# SPY_SCH.net
KiCad netlist of a schematic drawn in EAGLE
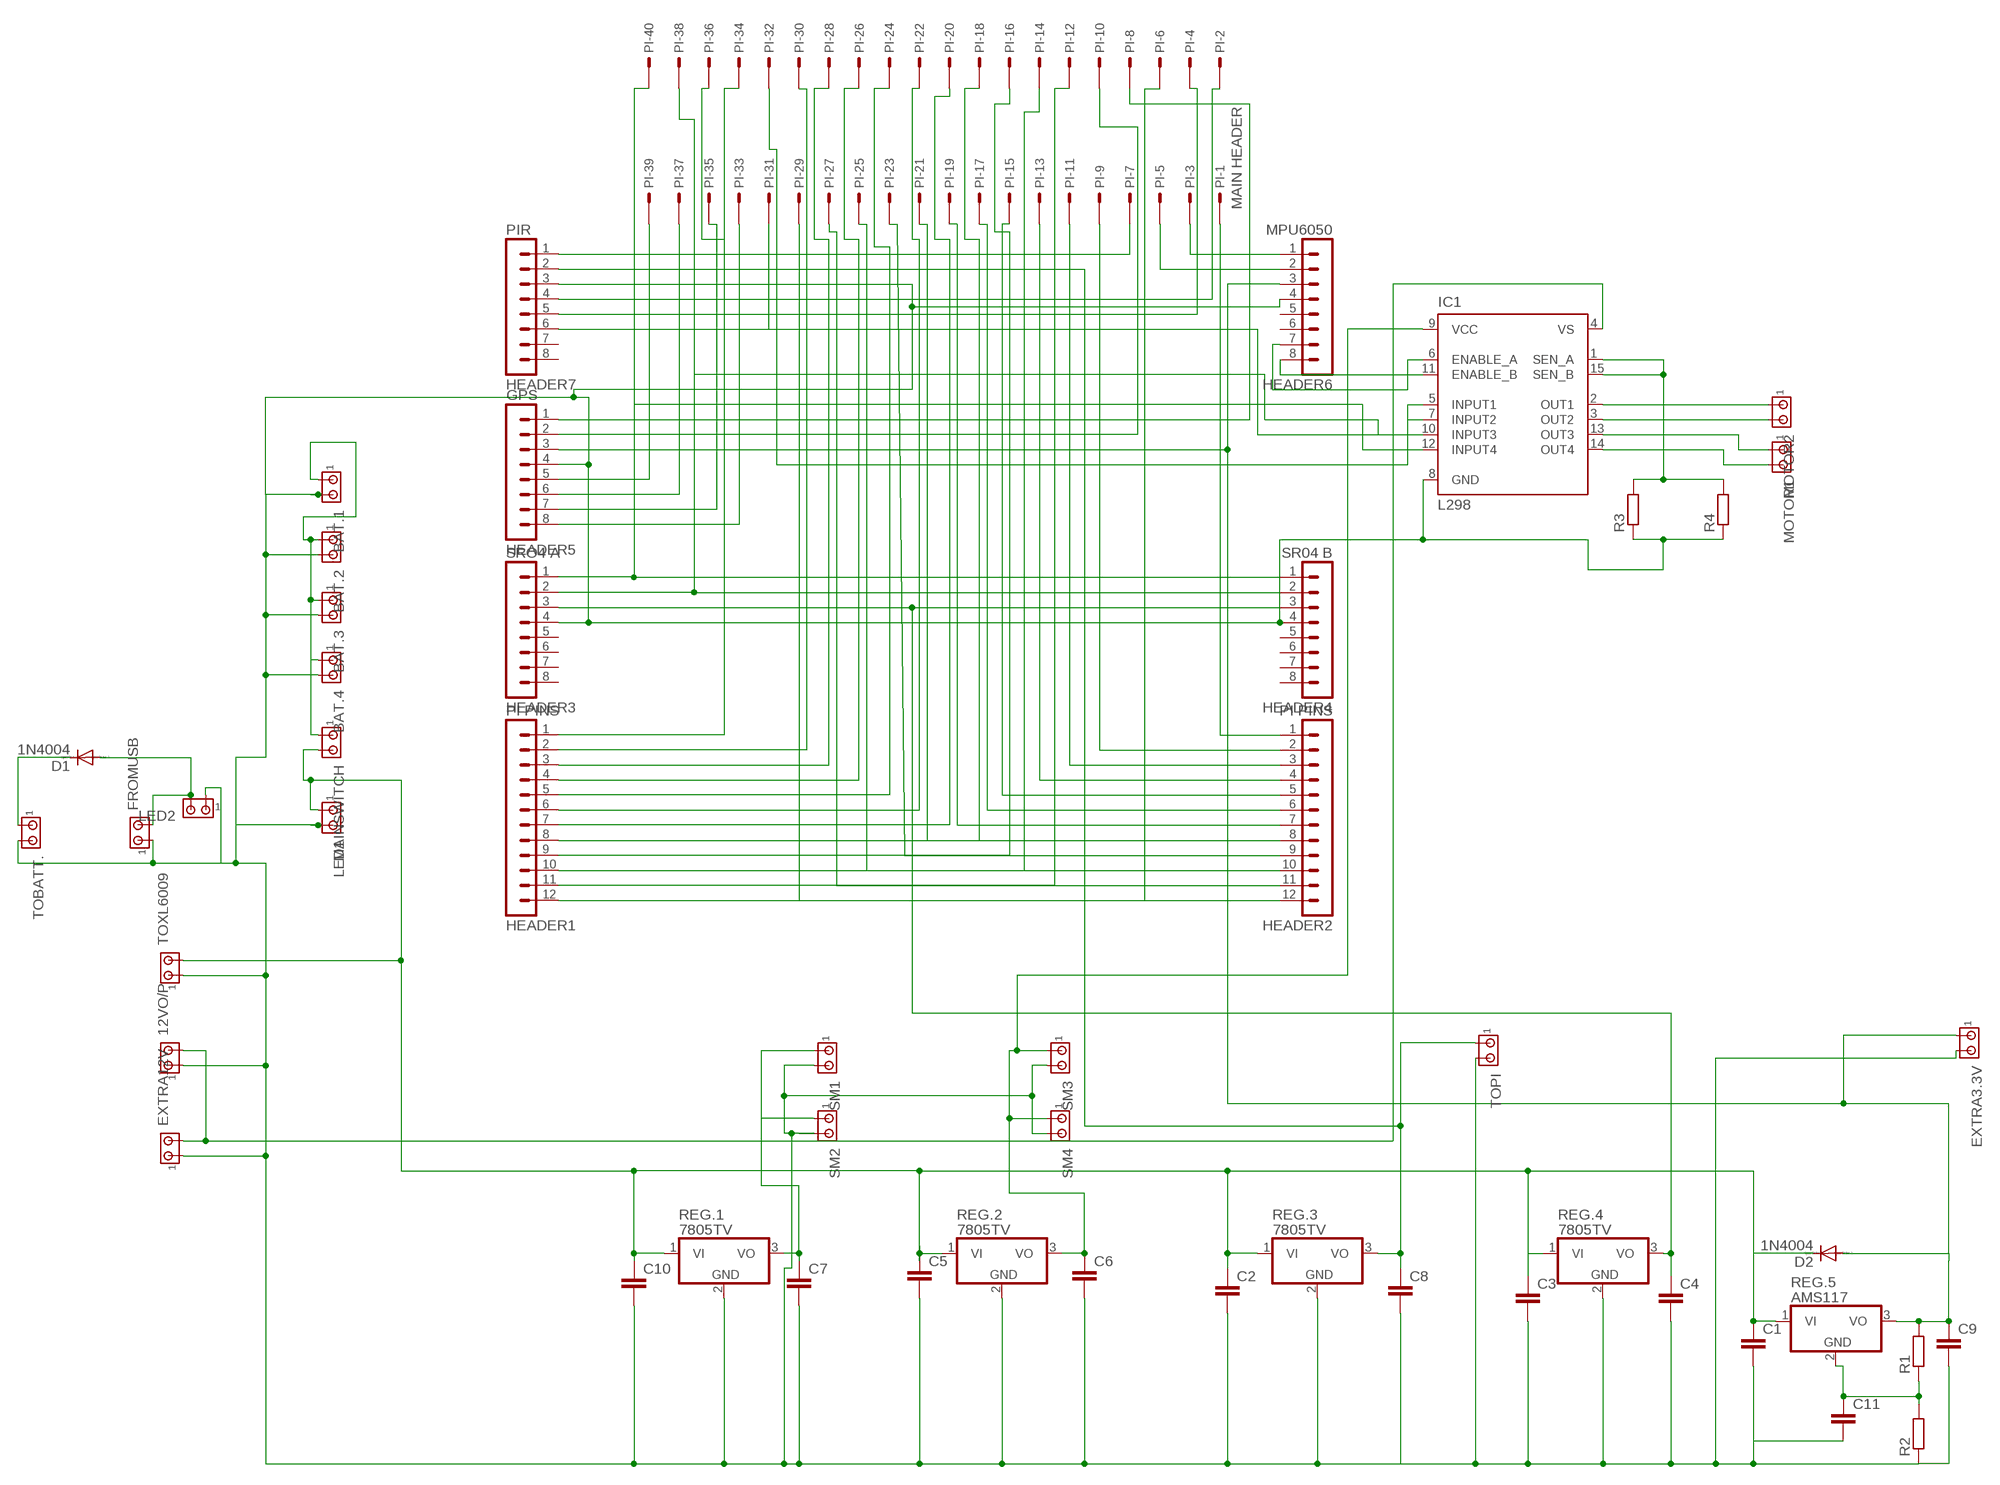
[diagram p0: schematic, sheet 1]

(export (version "E")
  (design (tool "Eeschema 10.0.6"))
  (components
    (comp (ref "12VO/P")
      (value "MTA02-156")
      (footprint "eagle-import:1X2MTA")
      (libsource (lib "eagle-import") (part "MTA02-156"))
    )
    (comp (ref "BAT.1")
      (value "MTA02-156")
      (footprint "eagle-import:1X2MTA")
      (libsource (lib "eagle-import") (part "MTA02-156"))
    )
    (comp (ref "BAT.2")
      (value "MTA02-156")
      (footprint "eagle-import:1X2MTA")
      (libsource (lib "eagle-import") (part "MTA02-156"))
    )
    (comp (ref "BAT.3")
      (value "MTA02-156")
      (footprint "eagle-import:1X2MTA")
      (libsource (lib "eagle-import") (part "MTA02-156"))
    )
    (comp (ref "BAT.4")
      (value "MTA02-156")
      (footprint "eagle-import:1X2MTA")
      (libsource (lib "eagle-import") (part "MTA02-156"))
    )
    (comp (ref "C1")
      (value "C2,5-3")
      (footprint "eagle-import:C2.5-3")
      (libsource (lib "eagle-import") (part "C2,5-3"))
    )
    (comp (ref "C2")
      (value "C2,5-3")
      (footprint "eagle-import:C2.5-3")
      (libsource (lib "eagle-import") (part "C2,5-3"))
    )
    (comp (ref "C3")
      (value "C2,5-3")
      (footprint "eagle-import:C2.5-3")
      (libsource (lib "eagle-import") (part "C2,5-3"))
    )
    (comp (ref "C4")
      (value "C2,5-3")
      (footprint "eagle-import:C2.5-3")
      (libsource (lib "eagle-import") (part "C2,5-3"))
    )
    (comp (ref "C5")
      (value "C2,5-3")
      (footprint "eagle-import:C2.5-3")
      (libsource (lib "eagle-import") (part "C2,5-3"))
    )
    (comp (ref "C6")
      (value "C2,5-3")
      (footprint "eagle-import:C2.5-3")
      (libsource (lib "eagle-import") (part "C2,5-3"))
    )
    (comp (ref "C7")
      (value "C2,5-3")
      (footprint "eagle-import:C2.5-3")
      (libsource (lib "eagle-import") (part "C2,5-3"))
    )
    (comp (ref "C8")
      (value "C2,5-3")
      (footprint "eagle-import:C2.5-3")
      (libsource (lib "eagle-import") (part "C2,5-3"))
    )
    (comp (ref "C9")
      (value "C2,5-3")
      (footprint "eagle-import:C2.5-3")
      (libsource (lib "eagle-import") (part "C2,5-3"))
    )
    (comp (ref "C10")
      (value "C2,5-3")
      (footprint "eagle-import:C2.5-3")
      (libsource (lib "eagle-import") (part "C2,5-3"))
    )
    (comp (ref "C11")
      (value "C2,5-3")
      (footprint "eagle-import:C2.5-3")
      (libsource (lib "eagle-import") (part "C2,5-3"))
    )
    (comp (ref "D1")
      (value "1N4004")
      (footprint "eagle-import:DO41-10")
      (libsource (lib "eagle-import") (part "1N4004"))
    )
    (comp (ref "D2")
      (value "1N4004")
      (footprint "eagle-import:DO41-10")
      (libsource (lib "eagle-import") (part "1N4004"))
    )
    (comp (ref "EXTRA3.3V")
      (value "MTA02-156")
      (footprint "eagle-import:1X2MTA")
      (libsource (lib "eagle-import") (part "MTA02-156"))
    )
    (comp (ref "EXTRA12V")
      (value "MTA02-156")
      (footprint "eagle-import:1X2MTA")
      (libsource (lib "eagle-import") (part "MTA02-156"))
    )
    (comp (ref "FROMUSB")
      (value "MTA02-156")
      (footprint "eagle-import:1X2MTA")
      (libsource (lib "eagle-import") (part "MTA02-156"))
    )
    (comp (ref "HEADER1")
      (value "PI PINS")
      (footprint "eagle-import:MA12-1W")
      (libsource (lib "eagle-import") (part "MA12-1W"))
    )
    (comp (ref "HEADER2")
      (value "PI PINS")
      (footprint "eagle-import:MA12-1W")
      (libsource (lib "eagle-import") (part "MA12-1W"))
    )
    (comp (ref "HEADER3")
      (value "SRO4 A")
      (footprint "eagle-import:MA08-1")
      (libsource (lib "eagle-import") (part "MA08-1"))
    )
    (comp (ref "HEADER4")
      (value "SR04 B")
      (footprint "eagle-import:MA08-1")
      (libsource (lib "eagle-import") (part "MA08-1"))
    )
    (comp (ref "HEADER5")
      (value "GPS")
      (footprint "eagle-import:MA08-1")
      (libsource (lib "eagle-import") (part "MA08-1"))
    )
    (comp (ref "HEADER6")
      (value "MPU6050")
      (footprint "eagle-import:MA08-1")
      (libsource (lib "eagle-import") (part "MA08-1"))
    )
    (comp (ref "HEADER7")
      (value "PIR")
      (footprint "eagle-import:MA08-1")
      (libsource (lib "eagle-import") (part "MA08-1"))
    )
    (comp (ref "IC1")
      (value "L298")
      (footprint "eagle-import:MULTIWATT-15")
      (fields (field (name "MPN") "L298N"))
      (libsource (lib "eagle-import") (part "L298"))
    )
    (comp (ref "LED1")
      (value "MTA02-156")
      (footprint "eagle-import:1X2MTA")
      (libsource (lib "eagle-import") (part "MTA02-156"))
    )
    (comp (ref "LED2")
      (value "MTA02-156")
      (footprint "eagle-import:1X2MTA")
      (libsource (lib "eagle-import") (part "MTA02-156"))
    )
    (comp (ref "MAINSWITCH")
      (value "MTA02-156")
      (footprint "eagle-import:1X2MTA")
      (libsource (lib "eagle-import") (part "MTA02-156"))
    )
    (comp (ref "MOTOR1")
      (value "MTA02-156")
      (footprint "eagle-import:1X2MTA")
      (libsource (lib "eagle-import") (part "MTA02-156"))
    )
    (comp (ref "MOTOR2")
      (value "MTA02-156")
      (footprint "eagle-import:1X2MTA")
      (libsource (lib "eagle-import") (part "MTA02-156"))
    )
    (comp (ref "PI")
      (value "MAIN HEADER")
      (footprint "eagle-import:057-040-1")
      (libsource (lib "eagle-import") (part "057-040-1"))
    )
    (comp (ref "R1")
      (value "R-EU_0309/12")
      (footprint "eagle-import:0309_12")
      (libsource (lib "eagle-import") (part "R-EU_0309/12"))
    )
    (comp (ref "R2")
      (value "R-EU_0309/12")
      (footprint "eagle-import:0309_12")
      (libsource (lib "eagle-import") (part "R-EU_0309/12"))
    )
    (comp (ref "R3")
      (value "R-EU_0309/12")
      (footprint "eagle-import:0309_12")
      (libsource (lib "eagle-import") (part "R-EU_0309/12"))
    )
    (comp (ref "R4")
      (value "R-EU_0309/12")
      (footprint "eagle-import:0309_12")
      (libsource (lib "eagle-import") (part "R-EU_0309/12"))
    )
    (comp (ref "REG.1")
      (value "7805TV")
      (footprint "eagle-import:TO220V")
      (libsource (lib "eagle-import") (part "78TV05"))
    )
    (comp (ref "REG.2")
      (value "7805TV")
      (footprint "eagle-import:TO220V")
      (libsource (lib "eagle-import") (part "78TV05"))
    )
    (comp (ref "REG.3")
      (value "7805TV")
      (footprint "eagle-import:TO220V")
      (libsource (lib "eagle-import") (part "78TV05"))
    )
    (comp (ref "REG.4")
      (value "7805TV")
      (footprint "eagle-import:TO220V")
      (libsource (lib "eagle-import") (part "78TV05"))
    )
    (comp (ref "REG.5")
      (value "AMS117")
      (footprint "eagle-import:TO220V")
      (libsource (lib "eagle-import") (part "78TV05"))
    )
    (comp (ref "SM1")
      (value "MTA02-156")
      (footprint "eagle-import:1X2MTA")
      (libsource (lib "eagle-import") (part "MTA02-156"))
    )
    (comp (ref "SM2")
      (value "MTA02-156")
      (footprint "eagle-import:1X2MTA")
      (libsource (lib "eagle-import") (part "MTA02-156"))
    )
    (comp (ref "SM3")
      (value "MTA02-156")
      (footprint "eagle-import:1X2MTA")
      (libsource (lib "eagle-import") (part "MTA02-156"))
    )
    (comp (ref "SM4")
      (value "MTA02-156")
      (footprint "eagle-import:1X2MTA")
      (libsource (lib "eagle-import") (part "MTA02-156"))
    )
    (comp (ref "TOBATT.")
      (value "MTA02-156")
      (footprint "eagle-import:1X2MTA")
      (libsource (lib "eagle-import") (part "MTA02-156"))
    )
    (comp (ref "TOPI")
      (value "MTA02-156")
      (footprint "eagle-import:1X2MTA")
      (libsource (lib "eagle-import") (part "MTA02-156"))
    )
    (comp (ref "TOXL6009")
      (value "MTA02-156")
      (footprint "eagle-import:1X2MTA")
      (libsource (lib "eagle-import") (part "MTA02-156"))
    )
  )
  (nets
    (net (code "1") (name "Net-(BAT.1-Pad1)") (class "Default")
      (node (ref "BAT.1") (pin "1") (pinfunction "1_1") (pintype "passive"))
      (node (ref "BAT.2") (pin "1") (pinfunction "1_1") (pintype "passive"))
      (node (ref "BAT.3") (pin "1") (pinfunction "1_1") (pintype "passive"))
      (node (ref "BAT.4") (pin "1") (pinfunction "1_1") (pintype "passive"))
      (node (ref "MAINSWITCH") (pin "1") (pinfunction "1_1") (pintype "passive"))
    )
    (net (code "2") (name "Net-(D1-PadA)") (class "Default")
      (node (ref "D1") (pin "A") (pinfunction "A_A") (pintype "passive"))
      (node (ref "FROMUSB") (pin "2") (pinfunction "2_2") (pintype "passive"))
      (node (ref "LED2") (pin "2") (pinfunction "2_2") (pintype "passive"))
    )
    (net (code "3") (name "Net-(D1-PadC)") (class "Default")
      (node (ref "D1") (pin "C") (pinfunction "C_C") (pintype "passive"))
      (node (ref "TOBATT.") (pin "1") (pinfunction "1_1") (pintype "passive"))
    )
    (net (code "4") (name "Net-(IC1-ENABLE_A)") (class "Default")
      (node (ref "HEADER6") (pin "7") (pinfunction "7_7") (pintype "passive"))
      (node (ref "IC1") (pin "6") (pinfunction "ENABLE_A_6") (pintype "input"))
    )
    (net (code "5") (name "Net-(IC1-ENABLE_B)") (class "Default")
      (node (ref "HEADER6") (pin "8") (pinfunction "8_8") (pintype "passive"))
      (node (ref "IC1") (pin "11") (pinfunction "ENABLE_B_11") (pintype "input"))
    )
    (net (code "6") (name "Net-(IC1-GND)") (class "Default")
      (node (ref "12VO/P") (pin "1") (pinfunction "1_1") (pintype "passive"))
      (node (ref "BAT.1") (pin "2") (pinfunction "2_2") (pintype "passive"))
      (node (ref "BAT.2") (pin "2") (pinfunction "2_2") (pintype "passive"))
      (node (ref "BAT.3") (pin "2") (pinfunction "2_2") (pintype "passive"))
      (node (ref "BAT.4") (pin "2") (pinfunction "2_2") (pintype "passive"))
      (node (ref "C1") (pin "2") (pinfunction "2_2") (pintype "passive"))
      (node (ref "C10") (pin "2") (pinfunction "2_2") (pintype "passive"))
      (node (ref "C11") (pin "2") (pinfunction "2_2") (pintype "passive"))
      (node (ref "C2") (pin "2") (pinfunction "2_2") (pintype "passive"))
      (node (ref "C3") (pin "2") (pinfunction "2_2") (pintype "passive"))
      (node (ref "C4") (pin "2") (pinfunction "2_2") (pintype "passive"))
      (node (ref "C5") (pin "2") (pinfunction "2_2") (pintype "passive"))
      (node (ref "C6") (pin "2") (pinfunction "2_2") (pintype "passive"))
      (node (ref "C7") (pin "2") (pinfunction "2_2") (pintype "passive"))
      (node (ref "C8") (pin "2") (pinfunction "2_2") (pintype "passive"))
      (node (ref "C9") (pin "2") (pinfunction "2_2") (pintype "passive"))
      (node (ref "EXTRA12V") (pin "1") (pinfunction "1_1") (pintype "passive"))
      (node (ref "EXTRA3.3V") (pin "2") (pinfunction "2_2") (pintype "passive"))
      (node (ref "FROMUSB") (pin "1") (pinfunction "1_1") (pintype "passive"))
      (node (ref "HEADER3") (pin "4") (pinfunction "4_4") (pintype "passive"))
      (node (ref "HEADER4") (pin "4") (pinfunction "4_4") (pintype "passive"))
      (node (ref "HEADER5") (pin "4") (pinfunction "4_4") (pintype "passive"))
      (node (ref "HEADER6") (pin "4") (pinfunction "4_4") (pintype "passive"))
      (node (ref "HEADER7") (pin "3") (pinfunction "3_3") (pintype "passive"))
      (node (ref "IC1") (pin "8") (pinfunction "GND_8") (pintype "power_in"))
      (node (ref "LED1") (pin "2") (pinfunction "2_2") (pintype "passive"))
      (node (ref "LED2") (pin "1") (pinfunction "1_1") (pintype "passive"))
      (node (ref "R2") (pin "1") (pinfunction "1_1") (pintype "passive"))
      (node (ref "R3") (pin "1") (pinfunction "1_1") (pintype "passive"))
      (node (ref "R4") (pin "1") (pinfunction "1_1") (pintype "passive"))
      (node (ref "REG.1") (pin "2") (pinfunction "GND_2") (pintype "passive"))
      (node (ref "REG.2") (pin "2") (pinfunction "GND_2") (pintype "passive"))
      (node (ref "REG.3") (pin "2") (pinfunction "GND_2") (pintype "passive"))
      (node (ref "REG.4") (pin "2") (pinfunction "GND_2") (pintype "passive"))
      (node (ref "SM1") (pin "2") (pinfunction "2_2") (pintype "passive"))
      (node (ref "SM2") (pin "2") (pinfunction "2_2") (pintype "passive"))
      (node (ref "SM3") (pin "2") (pinfunction "2_2") (pintype "passive"))
      (node (ref "SM4") (pin "2") (pinfunction "2_2") (pintype "passive"))
      (node (ref "TOBATT.") (pin "2") (pinfunction "2_2") (pintype "passive"))
      (node (ref "TOPI") (pin "2") (pinfunction "2_2") (pintype "passive"))
      (node (ref "TOXL6009") (pin "1") (pinfunction "1_1") (pintype "passive"))
    )
    (net (code "7") (name "Net-(IC1-INPUT1)") (class "Default")
      (node (ref "IC1") (pin "5") (pinfunction "INPUT1_5") (pintype "input"))
      (node (ref "PI") (pin "32") (pinfunction "S_32") (pintype "passive"))
    )
    (net (code "8") (name "Net-(IC1-INPUT2)") (class "Default")
      (node (ref "IC1") (pin "7") (pinfunction "INPUT2_7") (pintype "input"))
      (node (ref "PI") (pin "36") (pinfunction "S_36") (pintype "passive"))
    )
    (net (code "9") (name "Net-(IC1-INPUT3)") (class "Default")
      (node (ref "HEADER3") (pin "2") (pinfunction "2_2") (pintype "passive"))
      (node (ref "HEADER4") (pin "2") (pinfunction "2_2") (pintype "passive"))
      (node (ref "IC1") (pin "10") (pinfunction "INPUT3_10") (pintype "input"))
      (node (ref "PI") (pin "38") (pinfunction "S_38") (pintype "passive"))
    )
    (net (code "10") (name "Net-(IC1-INPUT4)") (class "Default")
      (node (ref "HEADER3") (pin "1") (pinfunction "1_1") (pintype "passive"))
      (node (ref "HEADER4") (pin "1") (pinfunction "1_1") (pintype "passive"))
      (node (ref "IC1") (pin "12") (pinfunction "INPUT4_12") (pintype "input"))
      (node (ref "PI") (pin "40") (pinfunction "S_40") (pintype "passive"))
    )
    (net (code "11") (name "Net-(IC1-OUT1)") (class "Default")
      (node (ref "IC1") (pin "2") (pinfunction "OUT1_2") (pintype "output"))
      (node (ref "MOTOR2") (pin "1") (pinfunction "1_1") (pintype "passive"))
    )
    (net (code "12") (name "Net-(IC1-OUT2)") (class "Default")
      (node (ref "IC1") (pin "3") (pinfunction "OUT2_3") (pintype "output"))
      (node (ref "MOTOR2") (pin "2") (pinfunction "2_2") (pintype "passive"))
    )
    (net (code "13") (name "Net-(IC1-OUT3)") (class "Default")
      (node (ref "IC1") (pin "13") (pinfunction "OUT3_13") (pintype "output"))
      (node (ref "MOTOR1") (pin "1") (pinfunction "1_1") (pintype "passive"))
    )
    (net (code "14") (name "Net-(IC1-OUT4)") (class "Default")
      (node (ref "IC1") (pin "14") (pinfunction "OUT4_14") (pintype "output"))
      (node (ref "MOTOR1") (pin "2") (pinfunction "2_2") (pintype "passive"))
    )
    (net (code "15") (name "Net-(IC1-SEN_A)") (class "Default")
      (node (ref "IC1") (pin "1") (pinfunction "SEN_A_1") (pintype "input"))
      (node (ref "IC1") (pin "15") (pinfunction "SEN_B_15") (pintype "input"))
      (node (ref "R3") (pin "2") (pinfunction "2_2") (pintype "passive"))
      (node (ref "R4") (pin "2") (pinfunction "2_2") (pintype "passive"))
    )
    (net (code "16") (name "Net-(IC1-VCC)") (class "Default")
      (node (ref "C6") (pin "1") (pinfunction "1_1") (pintype "passive"))
      (node (ref "IC1") (pin "9") (pinfunction "VCC_9") (pintype "power_in"))
      (node (ref "REG.2") (pin "3") (pinfunction "VO_3") (pintype "passive"))
      (node (ref "SM3") (pin "1") (pinfunction "1_1") (pintype "passive"))
      (node (ref "SM4") (pin "1") (pinfunction "1_1") (pintype "passive"))
    )
    (net (code "17") (name "Net-(IC1-VS)") (class "Default")
      (node (ref "12VO/P") (pin "2") (pinfunction "2_2") (pintype "passive"))
      (node (ref "EXTRA12V") (pin "2") (pinfunction "2_2") (pintype "passive"))
      (node (ref "IC1") (pin "4") (pinfunction "VS_4") (pintype "power_in"))
    )
    (net (code "18") (name "Net-(PIA-S)") (class "Default")
      (node (ref "HEADER2") (pin "1") (pinfunction "1_1") (pintype "passive"))
      (node (ref "PI") (pin "1") (pinfunction "S_1") (pintype "passive"))
    )
    (net (code "19") (name "Net-(PIAA-S)") (class "Default")
      (node (ref "HEADER5") (pin "8") (pinfunction "8_8") (pintype "passive"))
      (node (ref "PI") (pin "33") (pinfunction "S_33") (pintype "passive"))
    )
    (net (code "20") (name "Net-(PIAB-S)") (class "Default")
      (node (ref "HEADER1") (pin "1") (pinfunction "1_1") (pintype "passive"))
      (node (ref "PI") (pin "34") (pinfunction "S_34") (pintype "passive"))
    )
    (net (code "21") (name "Net-(PIAC-S)") (class "Default")
      (node (ref "HEADER5") (pin "7") (pinfunction "7_7") (pintype "passive"))
      (node (ref "PI") (pin "35") (pinfunction "S_35") (pintype "passive"))
    )
    (net (code "22") (name "Net-(PIAE-S)") (class "Default")
      (node (ref "HEADER5") (pin "6") (pinfunction "6_6") (pintype "passive"))
      (node (ref "PI") (pin "37") (pinfunction "S_37") (pintype "passive"))
    )
    (net (code "23") (name "Net-(PIAG-S)") (class "Default")
      (node (ref "HEADER5") (pin "5") (pinfunction "5_5") (pintype "passive"))
      (node (ref "PI") (pin "39") (pinfunction "S_39") (pintype "passive"))
    )
    (net (code "24") (name "Net-(PIAH-S)") (class "Default")
      (node (ref "HEADER7") (pin "5") (pinfunction "5_5") (pintype "passive"))
      (node (ref "PI") (pin "4") (pinfunction "S_4") (pintype "passive"))
    )
    (net (code "25") (name "Net-(PIAJ-S)") (class "Default")
      (node (ref "HEADER6") (pin "2") (pinfunction "2_2") (pintype "passive"))
      (node (ref "PI") (pin "5") (pinfunction "S_5") (pintype "passive"))
    )
    (net (code "26") (name "Net-(PIAK-S)") (class "Default")
      (node (ref "HEADER1") (pin "12") (pinfunction "12_12") (pintype "passive"))
      (node (ref "PI") (pin "6") (pinfunction "S_6") (pintype "passive"))
    )
    (net (code "27") (name "Net-(PIAL-S)") (class "Default")
      (node (ref "HEADER7") (pin "1") (pinfunction "1_1") (pintype "passive"))
      (node (ref "PI") (pin "7") (pinfunction "S_7") (pintype "passive"))
    )
    (net (code "28") (name "Net-(PIAM-S)") (class "Default")
      (node (ref "HEADER5") (pin "1") (pinfunction "1_1") (pintype "passive"))
      (node (ref "PI") (pin "8") (pinfunction "S_8") (pintype "passive"))
    )
    (net (code "29") (name "Net-(PIAN-S)") (class "Default")
      (node (ref "HEADER2") (pin "2") (pinfunction "2_2") (pintype "passive"))
      (node (ref "PI") (pin "9") (pinfunction "S_9") (pintype "passive"))
    )
    (net (code "30") (name "Net-(PIB-S)") (class "Default")
      (node (ref "HEADER5") (pin "2") (pinfunction "2_2") (pintype "passive"))
      (node (ref "PI") (pin "10") (pinfunction "S_10") (pintype "passive"))
    )
    (net (code "31") (name "Net-(PIC-S)") (class "Default")
      (node (ref "HEADER2") (pin "3") (pinfunction "3_3") (pintype "passive"))
      (node (ref "PI") (pin "11") (pinfunction "S_11") (pintype "passive"))
    )
    (net (code "32") (name "Net-(PID-S)") (class "Default")
      (node (ref "HEADER1") (pin "11") (pinfunction "11_11") (pintype "passive"))
      (node (ref "PI") (pin "12") (pinfunction "S_12") (pintype "passive"))
    )
    (net (code "33") (name "Net-(PIE-S)") (class "Default")
      (node (ref "HEADER2") (pin "4") (pinfunction "4_4") (pintype "passive"))
      (node (ref "PI") (pin "13") (pinfunction "S_13") (pintype "passive"))
    )
    (net (code "34") (name "Net-(PIF-S)") (class "Default")
      (node (ref "HEADER1") (pin "10") (pinfunction "10_10") (pintype "passive"))
      (node (ref "PI") (pin "14") (pinfunction "S_14") (pintype "passive"))
    )
    (net (code "35") (name "Net-(PIG-S)") (class "Default")
      (node (ref "HEADER2") (pin "5") (pinfunction "5_5") (pintype "passive"))
      (node (ref "PI") (pin "15") (pinfunction "S_15") (pintype "passive"))
    )
    (net (code "36") (name "Net-(PIH-S)") (class "Default")
      (node (ref "HEADER1") (pin "9") (pinfunction "9_9") (pintype "passive"))
      (node (ref "PI") (pin "16") (pinfunction "S_16") (pintype "passive"))
    )
    (net (code "37") (name "Net-(PII-S)") (class "Default")
      (node (ref "HEADER2") (pin "6") (pinfunction "6_6") (pintype "passive"))
      (node (ref "PI") (pin "17") (pinfunction "S_17") (pintype "passive"))
    )
    (net (code "38") (name "Net-(PIJ-S)") (class "Default")
      (node (ref "HEADER1") (pin "8") (pinfunction "8_8") (pintype "passive"))
      (node (ref "PI") (pin "18") (pinfunction "S_18") (pintype "passive"))
    )
    (net (code "39") (name "Net-(PIK-S)") (class "Default")
      (node (ref "HEADER2") (pin "7") (pinfunction "7_7") (pintype "passive"))
      (node (ref "PI") (pin "19") (pinfunction "S_19") (pintype "passive"))
    )
    (net (code "40") (name "Net-(PIL-S)") (class "Default")
      (node (ref "HEADER7") (pin "4") (pinfunction "4_4") (pintype "passive"))
      (node (ref "PI") (pin "2") (pinfunction "S_2") (pintype "passive"))
    )
    (net (code "41") (name "Net-(PIM-S)") (class "Default")
      (node (ref "HEADER1") (pin "7") (pinfunction "7_7") (pintype "passive"))
      (node (ref "PI") (pin "20") (pinfunction "S_20") (pintype "passive"))
    )
    (net (code "42") (name "Net-(PIN-S)") (class "Default")
      (node (ref "HEADER2") (pin "8") (pinfunction "8_8") (pintype "passive"))
      (node (ref "PI") (pin "21") (pinfunction "S_21") (pintype "passive"))
    )
    (net (code "43") (name "Net-(PIO-S)") (class "Default")
      (node (ref "HEADER1") (pin "6") (pinfunction "6_6") (pintype "passive"))
      (node (ref "PI") (pin "22") (pinfunction "S_22") (pintype "passive"))
    )
    (net (code "44") (name "Net-(PIP-S)") (class "Default")
      (node (ref "HEADER2") (pin "9") (pinfunction "9_9") (pintype "passive"))
      (node (ref "PI") (pin "23") (pinfunction "S_23") (pintype "passive"))
    )
    (net (code "45") (name "Net-(PIQ-S)") (class "Default")
      (node (ref "HEADER1") (pin "5") (pinfunction "5_5") (pintype "passive"))
      (node (ref "PI") (pin "24") (pinfunction "S_24") (pintype "passive"))
    )
    (net (code "46") (name "Net-(PIR-S)") (class "Default")
      (node (ref "HEADER2") (pin "10") (pinfunction "10_10") (pintype "passive"))
      (node (ref "PI") (pin "25") (pinfunction "S_25") (pintype "passive"))
    )
    (net (code "47") (name "Net-(PIS-S)") (class "Default")
      (node (ref "HEADER1") (pin "4") (pinfunction "4_4") (pintype "passive"))
      (node (ref "PI") (pin "26") (pinfunction "S_26") (pintype "passive"))
    )
    (net (code "48") (name "Net-(PIT-S)") (class "Default")
      (node (ref "HEADER2") (pin "11") (pinfunction "11_11") (pintype "passive"))
      (node (ref "PI") (pin "27") (pinfunction "S_27") (pintype "passive"))
    )
    (net (code "49") (name "Net-(PIU-S)") (class "Default")
      (node (ref "HEADER1") (pin "3") (pinfunction "3_3") (pintype "passive"))
      (node (ref "PI") (pin "28") (pinfunction "S_28") (pintype "passive"))
    )
    (net (code "50") (name "Net-(PIV-S)") (class "Default")
      (node (ref "HEADER2") (pin "12") (pinfunction "12_12") (pintype "passive"))
      (node (ref "PI") (pin "29") (pinfunction "S_29") (pintype "passive"))
    )
    (net (code "51") (name "Net-(PIW-S)") (class "Default")
      (node (ref "HEADER6") (pin "1") (pinfunction "1_1") (pintype "passive"))
      (node (ref "PI") (pin "3") (pinfunction "S_3") (pintype "passive"))
    )
    (net (code "52") (name "Net-(PIX-S)") (class "Default")
      (node (ref "HEADER1") (pin "2") (pinfunction "2_2") (pintype "passive"))
      (node (ref "PI") (pin "30") (pinfunction "S_30") (pintype "passive"))
    )
    (net (code "53") (name "Net-(PIY-S)") (class "Default")
      (node (ref "HEADER7") (pin "6") (pinfunction "6_6") (pintype "passive"))
      (node (ref "PI") (pin "31") (pinfunction "S_31") (pintype "passive"))
    )
    (net (code "54") (name "Net-(REG.1-VI)") (class "Default")
      (node (ref "C1") (pin "1") (pinfunction "1_1") (pintype "passive"))
      (node (ref "C10") (pin "1") (pinfunction "1_1") (pintype "passive"))
      (node (ref "C2") (pin "1") (pinfunction "1_1") (pintype "passive"))
      (node (ref "C3") (pin "1") (pinfunction "1_1") (pintype "passive"))
      (node (ref "C5") (pin "1") (pinfunction "1_1") (pintype "passive"))
      (node (ref "D2") (pin "C") (pinfunction "C_C") (pintype "passive"))
      (node (ref "LED1") (pin "1") (pinfunction "1_1") (pintype "passive"))
      (node (ref "MAINSWITCH") (pin "2") (pinfunction "2_2") (pintype "passive"))
      (node (ref "REG.1") (pin "1") (pinfunction "VI_1") (pintype "input"))
      (node (ref "REG.2") (pin "1") (pinfunction "VI_1") (pintype "input"))
      (node (ref "REG.3") (pin "1") (pinfunction "VI_1") (pintype "input"))
      (node (ref "REG.4") (pin "1") (pinfunction "VI_1") (pintype "input"))
      (node (ref "REG.5") (pin "1") (pinfunction "VI_1") (pintype "input"))
      (node (ref "TOXL6009") (pin "2") (pinfunction "2_2") (pintype "passive"))
    )
    (net (code "55") (name "Net-(REG.1-VO)") (class "Default")
      (node (ref "C7") (pin "1") (pinfunction "1_1") (pintype "passive"))
      (node (ref "REG.1") (pin "3") (pinfunction "VO_3") (pintype "passive"))
      (node (ref "SM1") (pin "1") (pinfunction "1_1") (pintype "passive"))
      (node (ref "SM2") (pin "1") (pinfunction "1_1") (pintype "passive"))
    )
    (net (code "56") (name "Net-(REG.3-VO)") (class "Default")
      (node (ref "C8") (pin "1") (pinfunction "1_1") (pintype "passive"))
      (node (ref "HEADER7") (pin "2") (pinfunction "2_2") (pintype "passive"))
      (node (ref "REG.3") (pin "3") (pinfunction "VO_3") (pintype "passive"))
      (node (ref "TOPI") (pin "1") (pinfunction "1_1") (pintype "passive"))
    )
    (net (code "57") (name "Net-(REG.4-VO)") (class "Default")
      (node (ref "C4") (pin "1") (pinfunction "1_1") (pintype "passive"))
      (node (ref "HEADER3") (pin "3") (pinfunction "3_3") (pintype "passive"))
      (node (ref "HEADER4") (pin "3") (pinfunction "3_3") (pintype "passive"))
      (node (ref "REG.4") (pin "3") (pinfunction "VO_3") (pintype "passive"))
    )
    (net (code "58") (name "Net-(REG.5-GND)") (class "Default")
      (node (ref "C11") (pin "1") (pinfunction "1_1") (pintype "passive"))
      (node (ref "R1") (pin "1") (pinfunction "1_1") (pintype "passive"))
      (node (ref "R2") (pin "2") (pinfunction "2_2") (pintype "passive"))
      (node (ref "REG.5") (pin "2") (pinfunction "GND_2") (pintype "passive"))
    )
    (net (code "59") (name "Net-(REG.5-VO)") (class "Default")
      (node (ref "C9") (pin "1") (pinfunction "1_1") (pintype "passive"))
      (node (ref "D2") (pin "A") (pinfunction "A_A") (pintype "passive"))
      (node (ref "EXTRA3.3V") (pin "1") (pinfunction "1_1") (pintype "passive"))
      (node (ref "HEADER5") (pin "3") (pinfunction "3_3") (pintype "passive"))
      (node (ref "HEADER6") (pin "3") (pinfunction "3_3") (pintype "passive"))
      (node (ref "R1") (pin "2") (pinfunction "2_2") (pintype "passive"))
      (node (ref "REG.5") (pin "3") (pinfunction "VO_3") (pintype "passive"))
    )
    (net (code "60") (name "unconnected-(HEADER3-Pad5)") (class "Default")
      (node (ref "HEADER3") (pin "5") (pinfunction "5_5") (pintype "passive"))
    )
    (net (code "61") (name "unconnected-(HEADER3-Pad6)") (class "Default")
      (node (ref "HEADER3") (pin "6") (pinfunction "6_6") (pintype "passive"))
    )
    (net (code "62") (name "unconnected-(HEADER3-Pad7)") (class "Default")
      (node (ref "HEADER3") (pin "7") (pinfunction "7_7") (pintype "passive"))
    )
    (net (code "63") (name "unconnected-(HEADER3-Pad8)") (class "Default")
      (node (ref "HEADER3") (pin "8") (pinfunction "8_8") (pintype "passive"))
    )
    (net (code "64") (name "unconnected-(HEADER4-Pad5)") (class "Default")
      (node (ref "HEADER4") (pin "5") (pinfunction "5_5") (pintype "passive"))
    )
    (net (code "65") (name "unconnected-(HEADER4-Pad6)") (class "Default")
      (node (ref "HEADER4") (pin "6") (pinfunction "6_6") (pintype "passive"))
    )
    (net (code "66") (name "unconnected-(HEADER4-Pad7)") (class "Default")
      (node (ref "HEADER4") (pin "7") (pinfunction "7_7") (pintype "passive"))
    )
    (net (code "67") (name "unconnected-(HEADER4-Pad8)") (class "Default")
      (node (ref "HEADER4") (pin "8") (pinfunction "8_8") (pintype "passive"))
    )
    (net (code "68") (name "unconnected-(HEADER6-Pad5)") (class "Default")
      (node (ref "HEADER6") (pin "5") (pinfunction "5_5") (pintype "passive"))
    )
    (net (code "69") (name "unconnected-(HEADER6-Pad6)") (class "Default")
      (node (ref "HEADER6") (pin "6") (pinfunction "6_6") (pintype "passive"))
    )
    (net (code "70") (name "unconnected-(HEADER7-Pad7)") (class "Default")
      (node (ref "HEADER7") (pin "7") (pinfunction "7_7") (pintype "passive"))
    )
    (net (code "71") (name "unconnected-(HEADER7-Pad8)") (class "Default")
      (node (ref "HEADER7") (pin "8") (pinfunction "8_8") (pintype "passive"))
    )
  )
)
